# Clock_Sch.net
KiCad netlist of a schematic drawn in Altium Designer
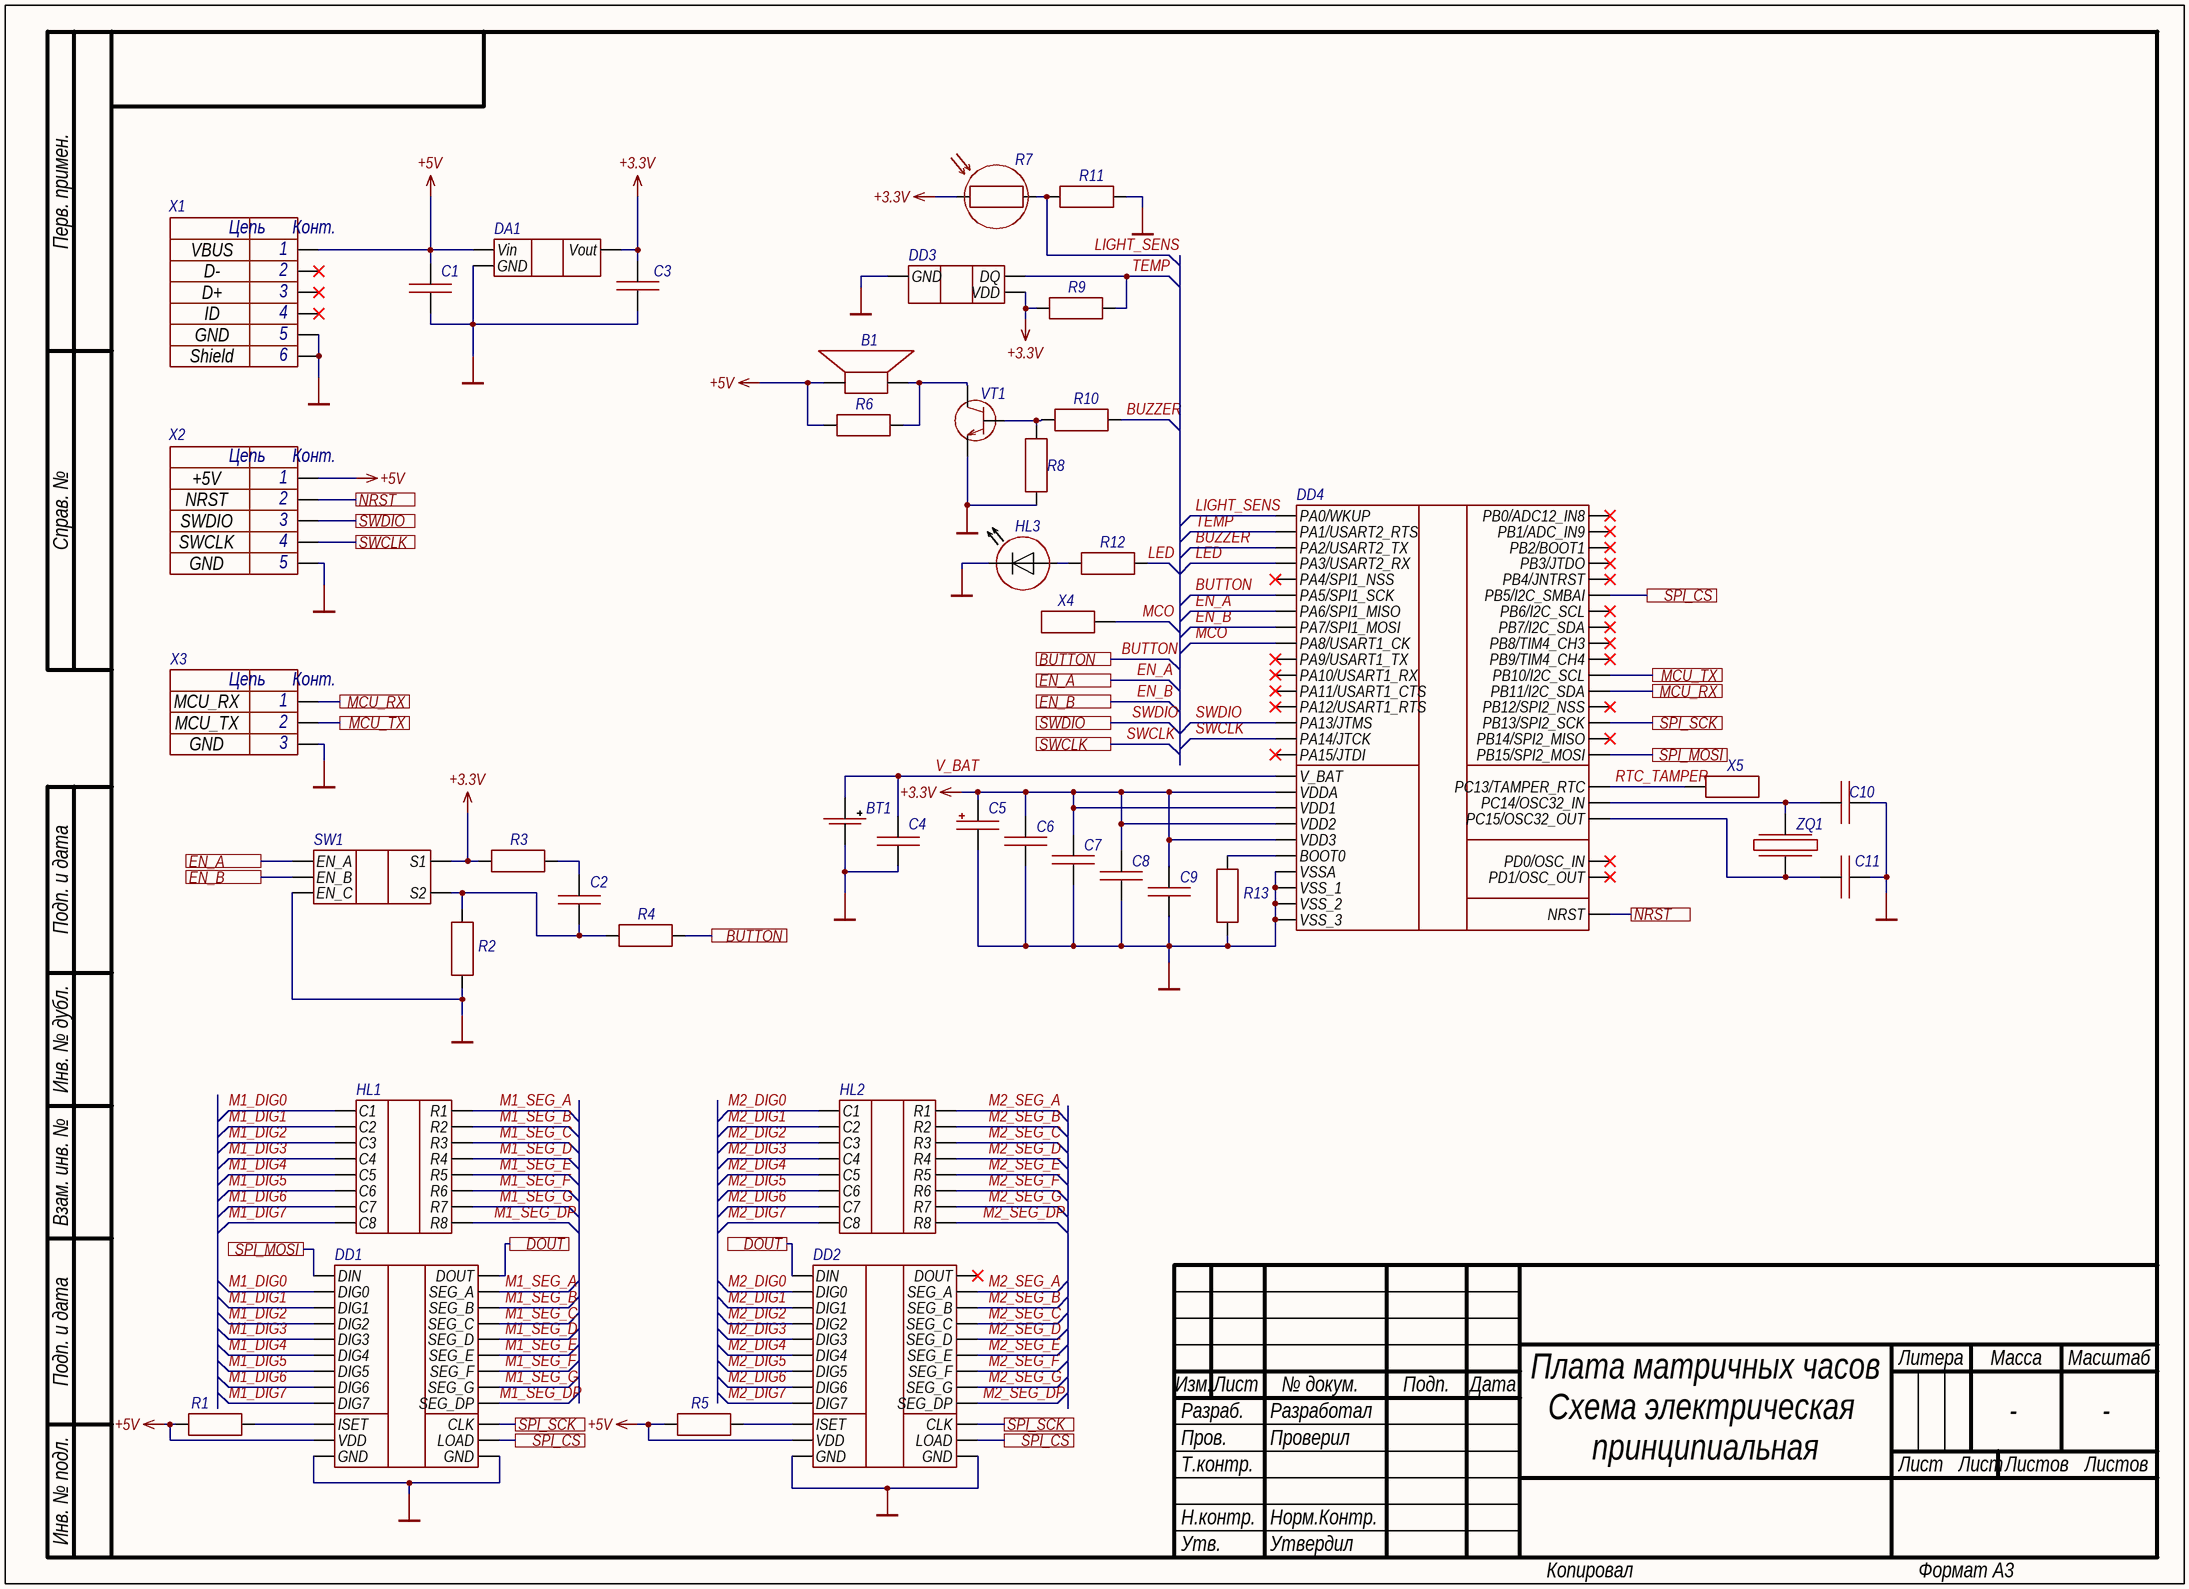
[diagram p0: Clock_Sch.SchDoc]

(export (version "E")
  (design (tool "Eeschema 10.0.6"))
  (components
    (comp (ref "B1")
      (value "AI-1223-TWT-12V-R")
      (footprint "Buzzer_12mm")
      (description "ELECTRO-MECHANICAL AUDIO INDICATOR")
      (libsource (lib "Indicators") (part "AI-1223-TWT-12V-R"))
    )
    (comp (ref "BT1")
      (value "CR-2032/F2N")
      (footprint "CR2032/F2N")
      (description "Coin, 20.0mm Lithium Manganese Dioxide 3 V Battery Non-Rechargeable (Primary)")
      (libsource (lib "Voltage Converters") (part "CR-2032/F2N"))
    )
    (comp (ref "C1")
      (value "C0603C334K4RACTU")
      (footprint "CAP_0603")
      (description "0.33 µF ±10% 16V Ceramic Capacitor X7R 0603 (1608 Metric)")
      (libsource (lib "Capacitors") (part "C0603C334K4RACTU"))
    )
    (comp (ref "C2")
      (value "C0603C104K9RACTU")
      (footprint "CAP_0603")
      (description "0.1 µF ±10% 6.3V Ceramic Capacitor X7R 0603 (1608 Metric)")
      (libsource (lib "Capacitors") (part "C0603C104K9RACTU"))
    )
    (comp (ref "C3")
      (value "C0603C104K9RACTU")
      (footprint "CAP_0603")
      (description "0.1 µF ±10% 6.3V Ceramic Capacitor X7R 0603 (1608 Metric)")
      (libsource (lib "Capacitors") (part "C0603C104K9RACTU"))
    )
    (comp (ref "C4")
      (value "C0603C104K9RACTU")
      (footprint "CAP_0603")
      (description "0.1 µF ±10% 6.3V Ceramic Capacitor X7R 0603 (1608 Metric)")
      (libsource (lib "Capacitors") (part "C0603C104K9RACTU"))
    )
    (comp (ref "C5")
      (value "T491A475K025AH")
      (footprint "CAP_A")
      (description "4.7uF 25V A CASE 10% (3.2 X 1.6 X 1.6mm) Inward L SMD 3216-18 6 Ohm 125°C Automotive T/R")
      (libsource (lib "Capacitors") (part "T491A475K025AH"))
    )
    (comp (ref "C6")
      (value "C0603C104K9RACTU")
      (footprint "CAP_0603")
      (description "0.1 µF ±10% 6.3V Ceramic Capacitor X7R 0603 (1608 Metric)")
      (libsource (lib "Capacitors") (part "C0603C104K9RACTU"))
    )
    (comp (ref "C7")
      (value "C0603C104K9RACTU")
      (footprint "CAP_0603")
      (description "0.1 µF ±10% 6.3V Ceramic Capacitor X7R 0603 (1608 Metric)")
      (libsource (lib "Capacitors") (part "C0603C104K9RACTU"))
    )
    (comp (ref "C8")
      (value "C0603C104K9RACTU")
      (footprint "CAP_0603")
      (description "0.1 µF ±10% 6.3V Ceramic Capacitor X7R 0603 (1608 Metric)")
      (libsource (lib "Capacitors") (part "C0603C104K9RACTU"))
    )
    (comp (ref "C9")
      (value "C0603C104K9RACTU")
      (footprint "CAP_0603")
      (description "0.1 µF ±10% 6.3V Ceramic Capacitor X7R 0603 (1608 Metric)")
      (libsource (lib "Capacitors") (part "C0603C104K9RACTU"))
    )
    (comp (ref "C10")
      (value "C0603C220G8GACTU")
      (footprint "CAP_0603")
      (description "22 pF ± 2% 10V Ceramic Capacitor 0603 (1608 metric)")
      (libsource (lib "Capacitors") (part "C0603C220G8GACTU"))
    )
    (comp (ref "C11")
      (value "C0603C220G8GACTU")
      (footprint "CAP_0603")
      (description "22 pF ± 2% 10V Ceramic Capacitor 0603 (1608 metric)")
      (libsource (lib "Capacitors") (part "C0603C220G8GACTU"))
    )
    (comp (ref "DA1")
      (value "L78L33ABUTR")
      (footprint "SOT-89")
      (description "Linear Voltage Regulators 3.3V 0.1A Positive")
      (libsource (lib "Voltage Converters") (part "L78L33ABUTR"))
    )
    (comp (ref "DD1")
      (value "MAX7219CWG")
      (footprint "SOIC-24W")
      (description "LED Display Drivers Serially Interfaced, 8-Digit, LED Display Drivers")
      (libsource (lib "Indicators") (part "MAX7219CWG"))
    )
    (comp (ref "DD2")
      (value "MAX7219CWG")
      (footprint "SOIC-24W")
      (description "LED Display Drivers Serially Interfaced, 8-Digit, LED Display Drivers")
      (libsource (lib "Indicators") (part "MAX7219CWG"))
    )
    (comp (ref "DD3")
      (value "DS18B20+")
      (footprint "TO-92")
      (description "Thermostats Programmable Resolution 1-Wire Digital Thermometer")
      (libsource (lib "Sensors") (part "DS18B20+"))
    )
    (comp (ref "DD4")
      (value "STM32F103C8T6")
      (footprint "LQFP48")
      (description "ARM Microcontrollers - MCU 32BIT Cortex M3 64KB 20KB RAM 2X12 ADC")
      (libsource (lib "Microcontrollers") (part "STM32F103C8T6"))
    )
    (comp (ref "HL1")
      (value "TC15-11GWA")
      (footprint "TC15-11")
      (description "LED Displays & Accessories Dot Matrix Grn 568nm Common Cathode")
      (libsource (lib "Indicators") (part "TC15-11GWA"))
    )
    (comp (ref "HL2")
      (value "TC15-11GWA")
      (footprint "TC15-11")
      (description "LED Displays & Accessories Dot Matrix Grn 568nm Common Cathode")
      (libsource (lib "Indicators") (part "TC15-11GWA"))
    )
    (comp (ref "HL3")
      (value "L_0805")
      (footprint "L_0805_Green")
      (description "0805 SMD LED")
      (libsource (lib "Indicators") (part "L_0805"))
    )
    (comp (ref "R1")
      (value "RC0805FR-0739KL")
      (footprint "Res_0805")
      (description "39 kOhm, 1% 0.125W 0805")
      (libsource (lib "Resistors") (part "RC0805FR-0739KL"))
    )
    (comp (ref "R2")
      (value "RC0805FR-071KL")
      (footprint "Res_0805")
      (description "1 kOhm, 1% 0.125W 0805")
      (libsource (lib "Resistors") (part "RC0805FR-071KL"))
    )
    (comp (ref "R3")
      (value "RC0805FR-07220RL")
      (footprint "Res_0805")
      (description "220 Ohm, 1% 0.125W 0805")
      (libsource (lib "Resistors") (part "RC0805FR-07220RL"))
    )
    (comp (ref "R4")
      (value "RC0805FR-07220RL")
      (footprint "Res_0805")
      (description "220 Ohm, 1% 0.125W 0805")
      (libsource (lib "Resistors") (part "RC0805FR-07220RL"))
    )
    (comp (ref "R5")
      (value "RC0805FR-0739KL")
      (footprint "Res_0805")
      (description "39 kOhm, 1% 0.125W 0805")
      (libsource (lib "Resistors") (part "RC0805FR-0739KL"))
    )
    (comp (ref "R6")
      (value "RC0805FR-071KL")
      (footprint "Res_0805")
      (description "1 kOhm, 1% 0.125W 0805")
      (libsource (lib "") (part "RC0805FR-071KL_1"))
    )
    (comp (ref "R7")
      (value "02-LDR2")
      (footprint "5mm LDR")
      (description "Photoresistor - 90mW - Light Resistance (10 Lux) 5 − 10Kohm - Dark Resistance 0.5Kohm - 5mm Dia")
      (libsource (lib "Sensors") (part "02-LDR2"))
    )
    (comp (ref "R8")
      (value "RC0805FR-0710KL")
      (footprint "Res_0805")
      (description "10 kOhm, 1% 0.125W 0805")
      (libsource (lib "") (part "RC0805FR-0710KL_1"))
    )
    (comp (ref "R9")
      (value "RC0805FR-074K7L")
      (footprint "Res_0805")
      (description "4.7 kOhm, 1% 0.125W 0805")
      (libsource (lib "Resistors") (part "RC0805FR-074K7L"))
    )
    (comp (ref "R10")
      (value "RC0805FR-071KL")
      (footprint "Res_0805")
      (description "1 kOhm, 1% 0.125W 0805")
      (libsource (lib "") (part "RC0805FR-071KL_1"))
    )
    (comp (ref "R11")
      (value "RC0805FR-0710KL")
      (footprint "Res_0805")
      (description "10 kOhm, 1% 0.125W 0805")
      (libsource (lib "Resistors") (part "RC0805FR-0710KL"))
    )
    (comp (ref "R12")
      (value "RC0805FR-071KL")
      (footprint "Res_0805")
      (description "1 kOhm, 1% 0.125W 0805")
      (libsource (lib "") (part "RC0805FR-071KL_1"))
    )
    (comp (ref "R13")
      (value "RC0805FR-071KL")
      (footprint "Res_0805")
      (description "1 kOhm, 1% 0.125W 0805")
      (libsource (lib "Resistors") (part "RC0805FR-071KL"))
    )
    (comp (ref "SW1")
      (value "EC12D1564402")
      (footprint "EC12D")
      (description "Encoder: incremental; Mounting: THT; 15imp/revol; 30000cycles")
      (libsource (lib "Switches") (part "EC12D1564402"))
    )
    (comp (ref "VT1")
      (value "BC817")
      (footprint "SOT-23")
      (description "Bipolar Transistors - BJT SOT23,NPN,0.8A,45V,GenPur")
      (libsource (lib "Transistors") (part "BC817"))
    )
    (comp (ref "X1")
      (value "47346-0001")
      (footprint "47346-0001")
      (description "USB - micro B USB 2.0 Receptacle Connector 5 Position Surface Mount, Right Angle")
      (libsource (lib "Connectors") (part "47346-0001"))
    )
    (comp (ref "X2")
      (value "PLS-5R (DS1022-1x5R)")
      (footprint "PLS-5 90' angle")
      (description "Male plug 2.54mm 1х5pin angled")
      (libsource (lib "Connectors") (part "PLS-5R (DS1022-1x5R)"))
    )
    (comp (ref "X3")
      (value "PLS-3 (DS1021-1x3)")
      (footprint "PLS-3")
      (description "Male plug 2.54mm 1x3pin straight type1")
      (libsource (lib "Connectors") (part "PLS-3 (DS1021-1x3)"))
    )
    (comp (ref "X4")
      (value "1-0.8-14-04")
      (footprint "1-0.8-14-04")
      (description "ГОСТ 16840-78")
      (libsource (lib "") (part "1-0.8-14-04_1"))
    )
    (comp (ref "X5")
      (value "1-0.8-14-04")
      (footprint "1-0.8-14-04")
      (description "ГОСТ 16840-78")
      (libsource (lib "Connectors") (part "1-0.8-14-04"))
    )
    (comp (ref "ZQ1")
      (value "MCRJ332768F1220HOW")
      (footprint "DT-38")
      (description "32.768kHz Crystal Resonator")
      (libsource (lib "XTALLs") (part "MCRJ332768F1220HOW"))
    )
  )
  (nets
    (net (code "1") (name "+3.3V") (class "Default")
      (node (ref "C3") (pin "2") (pinfunction "2_2") (pintype "passive"))
      (node (ref "C5") (pin "1") (pinfunction "1_1") (pintype "passive"))
      (node (ref "C6") (pin "2") (pinfunction "2_2") (pintype "passive"))
      (node (ref "C7") (pin "2") (pinfunction "2_2") (pintype "passive"))
      (node (ref "C8") (pin "2") (pinfunction "2_2") (pintype "passive"))
      (node (ref "C9") (pin "2") (pinfunction "2_2") (pintype "passive"))
      (node (ref "DA1") (pin "1") (pinfunction "Vout_1") (pintype "passive"))
      (node (ref "DD3") (pin "3") (pinfunction "VDD_3") (pintype "passive"))
      (node (ref "DD4") (pin "24") (pinfunction "VDD1_24") (pintype "passive"))
      (node (ref "DD4") (pin "36") (pinfunction "VDD2_36") (pintype "passive"))
      (node (ref "DD4") (pin "48") (pinfunction "VDD3_48") (pintype "passive"))
      (node (ref "DD4") (pin "9") (pinfunction "VDDA_9") (pintype "passive"))
      (node (ref "R3") (pin "1") (pinfunction "1_1") (pintype "passive"))
      (node (ref "R7") (pin "2") (pinfunction "2_2") (pintype "passive"))
      (node (ref "R9") (pin "2") (pinfunction "2_2") (pintype "passive"))
      (node (ref "SW1") (pin "D") (pinfunction "S1_D") (pintype "passive"))
    )
    (net (code "2") (name "+5V") (class "Default")
      (node (ref "B1") (pin "1") (pinfunction "1_1") (pintype "passive"))
      (node (ref "C1") (pin "2") (pinfunction "2_2") (pintype "passive"))
      (node (ref "DA1") (pin "3") (pinfunction "Vin_3") (pintype "passive"))
      (node (ref "DD1") (pin "19") (pinfunction "VDD_19") (pintype "passive"))
      (node (ref "DD2") (pin "19") (pinfunction "VDD_19") (pintype "passive"))
      (node (ref "R1") (pin "1") (pinfunction "1_1") (pintype "passive"))
      (node (ref "R5") (pin "1") (pinfunction "1_1") (pintype "passive"))
      (node (ref "R6") (pin "1") (pinfunction "1_1") (pintype "passive"))
      (node (ref "X1") (pin "1") (pinfunction "VBUS_1") (pintype "passive"))
      (node (ref "X2") (pin "1") (pinfunction "1_1") (pintype "passive"))
    )
    (net (code "3") (name "/BUTTON") (class "Default")
      (node (ref "DD4") (pin "15") (pinfunction "PA5/SPI1_SCK_15") (pintype "passive"))
      (node (ref "R4") (pin "2") (pinfunction "2_2") (pintype "passive"))
    )
    (net (code "4") (name "/BUZZER") (class "Default")
      (node (ref "DD4") (pin "12") (pinfunction "PA2/USART2_TX_12") (pintype "passive"))
      (node (ref "R10") (pin "2") (pinfunction "2_2") (pintype "passive"))
    )
    (net (code "5") (name "/DOUT") (class "Default")
      (node (ref "DD1") (pin "24") (pinfunction "DOUT_24") (pintype "passive"))
      (node (ref "DD2") (pin "1") (pinfunction "DIN_1") (pintype "passive"))
    )
    (net (code "6") (name "/EN_A") (class "Default")
      (node (ref "DD4") (pin "16") (pinfunction "PA6/SPI1_MISO_16") (pintype "passive"))
      (node (ref "SW1") (pin "A") (pinfunction "EN_A_A") (pintype "passive"))
    )
    (net (code "7") (name "/EN_B") (class "Default")
      (node (ref "DD4") (pin "17") (pinfunction "PA7/SPI1_MOSI_17") (pintype "passive"))
      (node (ref "SW1") (pin "B") (pinfunction "EN_B_B") (pintype "passive"))
    )
    (net (code "8") (name "/LED") (class "Default")
      (node (ref "DD4") (pin "13") (pinfunction "PA3/USART2_RX_13") (pintype "passive"))
      (node (ref "R12") (pin "2") (pinfunction "2_2") (pintype "passive"))
    )
    (net (code "9") (name "/LIGHT_SENS") (class "Default")
      (node (ref "DD4") (pin "10") (pinfunction "PA0/WKUP_10") (pintype "passive"))
      (node (ref "R11") (pin "2") (pinfunction "2_2") (pintype "passive"))
      (node (ref "R7") (pin "1") (pinfunction "1_1") (pintype "passive"))
    )
    (net (code "10") (name "/M1_DIG0") (class "Default")
      (node (ref "DD1") (pin "2") (pinfunction "DIG0_2") (pintype "passive"))
      (node (ref "HL1") (pin "13") (pinfunction "С1_13") (pintype "passive"))
    )
    (net (code "11") (name "/M1_DIG1") (class "Default")
      (node (ref "DD1") (pin "11") (pinfunction "DIG1_11") (pintype "passive"))
      (node (ref "HL1") (pin "3") (pinfunction "С2_3") (pintype "passive"))
    )
    (net (code "12") (name "/M1_DIG2") (class "Default")
      (node (ref "DD1") (pin "6") (pinfunction "DIG2_6") (pintype "passive"))
      (node (ref "HL1") (pin "4") (pinfunction "С3_4") (pintype "passive"))
    )
    (net (code "13") (name "/M1_DIG3") (class "Default")
      (node (ref "DD1") (pin "7") (pinfunction "DIG3_7") (pintype "passive"))
      (node (ref "HL1") (pin "10") (pinfunction "С4_10") (pintype "passive"))
    )
    (net (code "14") (name "/M1_DIG4") (class "Default")
      (node (ref "DD1") (pin "3") (pinfunction "DIG4_3") (pintype "passive"))
      (node (ref "HL1") (pin "6") (pinfunction "С5_6") (pintype "passive"))
    )
    (net (code "15") (name "/M1_DIG5") (class "Default")
      (node (ref "DD1") (pin "10") (pinfunction "DIG5_10") (pintype "passive"))
      (node (ref "HL1") (pin "11") (pinfunction "С6_11") (pintype "passive"))
    )
    (net (code "16") (name "/M1_DIG6") (class "Default")
      (node (ref "DD1") (pin "5") (pinfunction "DIG6_5") (pintype "passive"))
      (node (ref "HL1") (pin "15") (pinfunction "С7_15") (pintype "passive"))
    )
    (net (code "17") (name "/M1_DIG7") (class "Default")
      (node (ref "DD1") (pin "8") (pinfunction "DIG7_8") (pintype "passive"))
      (node (ref "HL1") (pin "16") (pinfunction "С8_16") (pintype "passive"))
    )
    (net (code "18") (name "/M1_SEG_A") (class "Default")
      (node (ref "DD1") (pin "14") (pinfunction "SEG_A_14") (pintype "passive"))
      (node (ref "HL1") (pin "9") (pinfunction "R1_9") (pintype "passive"))
    )
    (net (code "19") (name "/M1_SEG_B") (class "Default")
      (node (ref "DD1") (pin "16") (pinfunction "SEG_B_16") (pintype "passive"))
      (node (ref "HL1") (pin "14") (pinfunction "R2_14") (pintype "passive"))
    )
    (net (code "20") (name "/M1_SEG_C") (class "Default")
      (node (ref "DD1") (pin "20") (pinfunction "SEG_C_20") (pintype "passive"))
      (node (ref "HL1") (pin "8") (pinfunction "R3_8") (pintype "passive"))
    )
    (net (code "21") (name "/M1_SEG_D") (class "Default")
      (node (ref "DD1") (pin "23") (pinfunction "SEG_D_23") (pintype "passive"))
      (node (ref "HL1") (pin "12") (pinfunction "R4_12") (pintype "passive"))
    )
    (net (code "22") (name "/M1_SEG_DP") (class "Default")
      (node (ref "DD1") (pin "22") (pinfunction "SEG_DP_22") (pintype "passive"))
      (node (ref "HL1") (pin "5") (pinfunction "R8_5") (pintype "passive"))
    )
    (net (code "23") (name "/M1_SEG_E") (class "Default")
      (node (ref "DD1") (pin "21") (pinfunction "SEG_E_21") (pintype "passive"))
      (node (ref "HL1") (pin "1") (pinfunction "R5_1") (pintype "passive"))
    )
    (net (code "24") (name "/M1_SEG_F") (class "Default")
      (node (ref "DD1") (pin "15") (pinfunction "SEG_F_15") (pintype "passive"))
      (node (ref "HL1") (pin "7") (pinfunction "R6_7") (pintype "passive"))
    )
    (net (code "25") (name "/M1_SEG_G") (class "Default")
      (node (ref "DD1") (pin "17") (pinfunction "SEG_G_17") (pintype "passive"))
      (node (ref "HL1") (pin "2") (pinfunction "R7_2") (pintype "passive"))
    )
    (net (code "26") (name "/M2_DIG0") (class "Default")
      (node (ref "DD2") (pin "2") (pinfunction "DIG0_2") (pintype "passive"))
      (node (ref "HL2") (pin "13") (pinfunction "С1_13") (pintype "passive"))
    )
    (net (code "27") (name "/M2_DIG1") (class "Default")
      (node (ref "DD2") (pin "11") (pinfunction "DIG1_11") (pintype "passive"))
      (node (ref "HL2") (pin "3") (pinfunction "С2_3") (pintype "passive"))
    )
    (net (code "28") (name "/M2_DIG2") (class "Default")
      (node (ref "DD2") (pin "6") (pinfunction "DIG2_6") (pintype "passive"))
      (node (ref "HL2") (pin "4") (pinfunction "С3_4") (pintype "passive"))
    )
    (net (code "29") (name "/M2_DIG3") (class "Default")
      (node (ref "DD2") (pin "7") (pinfunction "DIG3_7") (pintype "passive"))
      (node (ref "HL2") (pin "10") (pinfunction "С4_10") (pintype "passive"))
    )
    (net (code "30") (name "/M2_DIG4") (class "Default")
      (node (ref "DD2") (pin "3") (pinfunction "DIG4_3") (pintype "passive"))
      (node (ref "HL2") (pin "6") (pinfunction "С5_6") (pintype "passive"))
    )
    (net (code "31") (name "/M2_DIG5") (class "Default")
      (node (ref "DD2") (pin "10") (pinfunction "DIG5_10") (pintype "passive"))
      (node (ref "HL2") (pin "11") (pinfunction "С6_11") (pintype "passive"))
    )
    (net (code "32") (name "/M2_DIG6") (class "Default")
      (node (ref "DD2") (pin "5") (pinfunction "DIG6_5") (pintype "passive"))
      (node (ref "HL2") (pin "15") (pinfunction "С7_15") (pintype "passive"))
    )
    (net (code "33") (name "/M2_DIG7") (class "Default")
      (node (ref "DD2") (pin "8") (pinfunction "DIG7_8") (pintype "passive"))
      (node (ref "HL2") (pin "16") (pinfunction "С8_16") (pintype "passive"))
    )
    (net (code "34") (name "/M2_SEG_A") (class "Default")
      (node (ref "DD2") (pin "14") (pinfunction "SEG_A_14") (pintype "passive"))
      (node (ref "HL2") (pin "9") (pinfunction "R1_9") (pintype "passive"))
    )
    (net (code "35") (name "/M2_SEG_B") (class "Default")
      (node (ref "DD2") (pin "16") (pinfunction "SEG_B_16") (pintype "passive"))
      (node (ref "HL2") (pin "14") (pinfunction "R2_14") (pintype "passive"))
    )
    (net (code "36") (name "/M2_SEG_C") (class "Default")
      (node (ref "DD2") (pin "20") (pinfunction "SEG_C_20") (pintype "passive"))
      (node (ref "HL2") (pin "8") (pinfunction "R3_8") (pintype "passive"))
    )
    (net (code "37") (name "/M2_SEG_D") (class "Default")
      (node (ref "DD2") (pin "23") (pinfunction "SEG_D_23") (pintype "passive"))
      (node (ref "HL2") (pin "12") (pinfunction "R4_12") (pintype "passive"))
    )
    (net (code "38") (name "/M2_SEG_DP") (class "Default")
      (node (ref "DD2") (pin "22") (pinfunction "SEG_DP_22") (pintype "passive"))
      (node (ref "HL2") (pin "5") (pinfunction "R8_5") (pintype "passive"))
    )
    (net (code "39") (name "/M2_SEG_E") (class "Default")
      (node (ref "DD2") (pin "21") (pinfunction "SEG_E_21") (pintype "passive"))
      (node (ref "HL2") (pin "1") (pinfunction "R5_1") (pintype "passive"))
    )
    (net (code "40") (name "/M2_SEG_F") (class "Default")
      (node (ref "DD2") (pin "15") (pinfunction "SEG_F_15") (pintype "passive"))
      (node (ref "HL2") (pin "7") (pinfunction "R6_7") (pintype "passive"))
    )
    (net (code "41") (name "/M2_SEG_G") (class "Default")
      (node (ref "DD2") (pin "17") (pinfunction "SEG_G_17") (pintype "passive"))
      (node (ref "HL2") (pin "2") (pinfunction "R7_2") (pintype "passive"))
    )
    (net (code "42") (name "/MCO") (class "Default")
      (node (ref "DD4") (pin "29") (pinfunction "PA8/USART1_CK_29") (pintype "passive"))
      (node (ref "X4") (pin "1") (pinfunction "1_1") (pintype "passive"))
    )
    (net (code "43") (name "/MCU_RX") (class "Default")
      (node (ref "DD4") (pin "22") (pinfunction "PB11/I2C_SDA_22") (pintype "passive"))
      (node (ref "X3") (pin "1") (pinfunction "1_1") (pintype "passive"))
    )
    (net (code "44") (name "/MCU_TX") (class "Default")
      (node (ref "DD4") (pin "21") (pinfunction "PB10/I2C_SCL_21") (pintype "passive"))
      (node (ref "X3") (pin "2") (pinfunction "2_2") (pintype "passive"))
    )
    (net (code "45") (name "/NRST") (class "Default")
      (node (ref "DD4") (pin "7") (pinfunction "NRST_7") (pintype "passive"))
      (node (ref "X2") (pin "2") (pinfunction "2_2") (pintype "passive"))
    )
    (net (code "46") (name "/RTC_TAMPER") (class "Default")
      (node (ref "DD4") (pin "2") (pinfunction "PC13/TAMPER_RTC_2") (pintype "passive"))
      (node (ref "X5") (pin "1") (pinfunction "1_1") (pintype "passive"))
    )
    (net (code "47") (name "/SPI_CS") (class "Default")
      (node (ref "DD1") (pin "12") (pinfunction "LOAD_12") (pintype "passive"))
      (node (ref "DD2") (pin "12") (pinfunction "LOAD_12") (pintype "passive"))
      (node (ref "DD4") (pin "41") (pinfunction "PB5/I2C_SMBAI_41") (pintype "passive"))
    )
    (net (code "48") (name "/SPI_MOSI") (class "Default")
      (node (ref "DD1") (pin "1") (pinfunction "DIN_1") (pintype "passive"))
      (node (ref "DD4") (pin "28") (pinfunction "PB15/SPI2_MOSI_28") (pintype "passive"))
    )
    (net (code "49") (name "/SPI_SCK") (class "Default")
      (node (ref "DD1") (pin "13") (pinfunction "CLK_13") (pintype "passive"))
      (node (ref "DD2") (pin "13") (pinfunction "CLK_13") (pintype "passive"))
      (node (ref "DD4") (pin "26") (pinfunction "PB13/SPI2_SCK_26") (pintype "passive"))
    )
    (net (code "50") (name "/SWCLK") (class "Default")
      (node (ref "DD4") (pin "37") (pinfunction "PA14/JTCK_37") (pintype "passive"))
      (node (ref "X2") (pin "4") (pinfunction "4_4") (pintype "passive"))
    )
    (net (code "51") (name "/SWDIO") (class "Default")
      (node (ref "DD4") (pin "34") (pinfunction "PA13/JTMS_34") (pintype "passive"))
      (node (ref "X2") (pin "3") (pinfunction "3_3") (pintype "passive"))
    )
    (net (code "52") (name "/TEMP") (class "Default")
      (node (ref "DD3") (pin "2") (pinfunction "DQ_2") (pintype "passive"))
      (node (ref "DD4") (pin "11") (pinfunction "PA1/USART2_RTS_11") (pintype "passive"))
      (node (ref "R9") (pin "1") (pinfunction "1_1") (pintype "passive"))
    )
    (net (code "53") (name "/V_BAT") (class "Default")
      (node (ref "BT1") (pin "1") (pinfunction "+_1") (pintype "passive"))
      (node (ref "C4") (pin "2") (pinfunction "2_2") (pintype "passive"))
      (node (ref "DD4") (pin "1") (pinfunction "V_BAT_1") (pintype "passive"))
    )
    (net (code "54") (name "GND") (class "Default")
      (node (ref "BT1") (pin "2") (pinfunction "-_2") (pintype "passive"))
      (node (ref "C1") (pin "1") (pinfunction "1_1") (pintype "passive"))
      (node (ref "C10") (pin "1") (pinfunction "1_1") (pintype "passive"))
      (node (ref "C11") (pin "1") (pinfunction "1_1") (pintype "passive"))
      (node (ref "C3") (pin "1") (pinfunction "1_1") (pintype "passive"))
      (node (ref "C4") (pin "1") (pinfunction "1_1") (pintype "passive"))
      (node (ref "C5") (pin "2") (pinfunction "2_2") (pintype "passive"))
      (node (ref "C6") (pin "1") (pinfunction "1_1") (pintype "passive"))
      (node (ref "C7") (pin "1") (pinfunction "1_1") (pintype "passive"))
      (node (ref "C8") (pin "1") (pinfunction "1_1") (pintype "passive"))
      (node (ref "C9") (pin "1") (pinfunction "1_1") (pintype "passive"))
      (node (ref "DA1") (pin "2") (pinfunction "GND_2") (pintype "passive"))
      (node (ref "DD1") (pin "4") (pinfunction "GND_4") (pintype "passive"))
      (node (ref "DD1") (pin "9") (pinfunction "GND_9") (pintype "passive"))
      (node (ref "DD2") (pin "4") (pinfunction "GND_4") (pintype "passive"))
      (node (ref "DD2") (pin "9") (pinfunction "GND_9") (pintype "passive"))
      (node (ref "DD3") (pin "1") (pinfunction "GND_1") (pintype "passive"))
      (node (ref "DD4") (pin "23") (pinfunction "VSS_1_23") (pintype "passive"))
      (node (ref "DD4") (pin "35") (pinfunction "VSS_2_35") (pintype "passive"))
      (node (ref "DD4") (pin "47") (pinfunction "VSS_3_47") (pintype "passive"))
      (node (ref "DD4") (pin "8") (pinfunction "VSSA_8") (pintype "passive"))
      (node (ref "HL3") (pin "2") (pinfunction "-_2") (pintype "passive"))
      (node (ref "R11") (pin "1") (pinfunction "1_1") (pintype "passive"))
      (node (ref "R13") (pin "1") (pinfunction "1_1") (pintype "passive"))
      (node (ref "R2") (pin "1") (pinfunction "1_1") (pintype "passive"))
      (node (ref "R8") (pin "1") (pinfunction "1_1") (pintype "passive"))
      (node (ref "SW1") (pin "C") (pinfunction "EN_C_C") (pintype "passive"))
      (node (ref "VT1") (pin "2") (pinfunction "Emitter_2") (pintype "passive"))
      (node (ref "X1") (pin "5") (pinfunction "GND_5") (pintype "passive"))
      (node (ref "X1") (pin "6") (pinfunction "Shield_6") (pintype "passive"))
      (node (ref "X2") (pin "5") (pinfunction "5_5") (pintype "passive"))
      (node (ref "X3") (pin "3") (pinfunction "3_3") (pintype "passive"))
    )
    (net (code "55") (name "Net-(C2-Pad2)") (class "Default")
      (node (ref "C2") (pin "2") (pinfunction "2_2") (pintype "passive"))
      (node (ref "R3") (pin "2") (pinfunction "2_2") (pintype "passive"))
    )
    (net (code "56") (name "Net-(DD1-ISET)") (class "Default")
      (node (ref "DD1") (pin "18") (pinfunction "ISET_18") (pintype "passive"))
      (node (ref "R1") (pin "2") (pinfunction "2_2") (pintype "passive"))
    )
    (net (code "57") (name "Net-(DD2-ISET)") (class "Default")
      (node (ref "DD2") (pin "18") (pinfunction "ISET_18") (pintype "passive"))
      (node (ref "R5") (pin "2") (pinfunction "2_2") (pintype "passive"))
    )
    (net (code "58") (name "Net-(DD4-BOOT0)") (class "Default")
      (node (ref "DD4") (pin "44") (pinfunction "BOOT0_44") (pintype "passive"))
      (node (ref "R13") (pin "2") (pinfunction "2_2") (pintype "passive"))
    )
    (net (code "59") (name "Net-(DD4-PC14{slash}OSC32_IN)") (class "Default")
      (node (ref "C10") (pin "2") (pinfunction "2_2") (pintype "passive"))
      (node (ref "DD4") (pin "3") (pinfunction "PC14/OSC32_IN_3") (pintype "passive"))
      (node (ref "ZQ1") (pin "2") (pinfunction "2_2") (pintype "passive"))
    )
    (net (code "60") (name "Net-(DD4-PC15{slash}OSC32_OUT)") (class "Default")
      (node (ref "C11") (pin "2") (pinfunction "2_2") (pintype "passive"))
      (node (ref "DD4") (pin "4") (pinfunction "PC15/OSC32_OUT_4") (pintype "passive"))
      (node (ref "ZQ1") (pin "1") (pinfunction "1_1") (pintype "passive"))
    )
    (net (code "61") (name "Net-(HL3-+)") (class "Default")
      (node (ref "HL3") (pin "1") (pinfunction "+_1") (pintype "passive"))
      (node (ref "R12") (pin "1") (pinfunction "1_1") (pintype "passive"))
    )
    (net (code "62") (name "Net-(SW1-S2)") (class "Default")
      (node (ref "C2") (pin "1") (pinfunction "1_1") (pintype "passive"))
      (node (ref "R2") (pin "2") (pinfunction "2_2") (pintype "passive"))
      (node (ref "R4") (pin "1") (pinfunction "1_1") (pintype "passive"))
      (node (ref "SW1") (pin "E") (pinfunction "S2_E") (pintype "passive"))
    )
    (net (code "63") (name "Net-(VT1-BASE)") (class "Default")
      (node (ref "R10") (pin "1") (pinfunction "1_1") (pintype "passive"))
      (node (ref "R8") (pin "2") (pinfunction "2_2") (pintype "passive"))
      (node (ref "VT1") (pin "1") (pinfunction "BASE_1") (pintype "passive"))
    )
    (net (code "64") (name "Net-(VT1-Collector)") (class "Default")
      (node (ref "B1") (pin "2") (pinfunction "2_2") (pintype "passive"))
      (node (ref "R6") (pin "2") (pinfunction "2_2") (pintype "passive"))
      (node (ref "VT1") (pin "3") (pinfunction "Collector_3") (pintype "passive"))
    )
    (net (code "65") (name "unconnected-(DD2-DOUT-Pad24)") (class "Default")
      (node (ref "DD2") (pin "24") (pinfunction "DOUT_24") (pintype "passive+no_connect"))
    )
    (net (code "66") (name "unconnected-(DD4-PA4{slash}SPI1_NSS-Pad14)") (class "Default")
      (node (ref "DD4") (pin "14") (pinfunction "PA4/SPI1_NSS_14") (pintype "passive+no_connect"))
    )
    (net (code "67") (name "unconnected-(DD4-PA9{slash}USART1_TX-Pad30)") (class "Default")
      (node (ref "DD4") (pin "30") (pinfunction "PA9/USART1_TX_30") (pintype "passive+no_connect"))
    )
    (net (code "68") (name "unconnected-(DD4-PA10{slash}USART1_RX-Pad31)") (class "Default")
      (node (ref "DD4") (pin "31") (pinfunction "PA10/USART1_RX_31") (pintype "passive+no_connect"))
    )
    (net (code "69") (name "unconnected-(DD4-PA11{slash}USART1_CTS-Pad32)") (class "Default")
      (node (ref "DD4") (pin "32") (pinfunction "PA11/USART1_CTS_32") (pintype "passive+no_connect"))
    )
    (net (code "70") (name "unconnected-(DD4-PA12{slash}USART1_RTS-Pad33)") (class "Default")
      (node (ref "DD4") (pin "33") (pinfunction "PA12/USART1_RTS_33") (pintype "passive+no_connect"))
    )
    (net (code "71") (name "unconnected-(DD4-PA15{slash}JTDI-Pad38)") (class "Default")
      (node (ref "DD4") (pin "38") (pinfunction "PA15/JTDI_38") (pintype "passive+no_connect"))
    )
    (net (code "72") (name "unconnected-(DD4-PB0{slash}ADC12_IN8-Pad18)") (class "Default")
      (node (ref "DD4") (pin "18") (pinfunction "PB0/ADC12_IN8_18") (pintype "passive+no_connect"))
    )
    (net (code "73") (name "unconnected-(DD4-PB1{slash}ADC_IN9-Pad19)") (class "Default")
      (node (ref "DD4") (pin "19") (pinfunction "PB1/ADC_IN9_19") (pintype "passive+no_connect"))
    )
    (net (code "74") (name "unconnected-(DD4-PB2{slash}BOOT1-Pad20)") (class "Default")
      (node (ref "DD4") (pin "20") (pinfunction "PB2/BOOT1_20") (pintype "passive+no_connect"))
    )
    (net (code "75") (name "unconnected-(DD4-PB3{slash}JTDO-Pad39)") (class "Default")
      (node (ref "DD4") (pin "39") (pinfunction "PB3/JTDO_39") (pintype "passive+no_connect"))
    )
    (net (code "76") (name "unconnected-(DD4-PB4{slash}JNTRST-Pad40)") (class "Default")
      (node (ref "DD4") (pin "40") (pinfunction "PB4/JNTRST_40") (pintype "passive+no_connect"))
    )
    (net (code "77") (name "unconnected-(DD4-PB6{slash}I2C_SCL-Pad42)") (class "Default")
      (node (ref "DD4") (pin "42") (pinfunction "PB6/I2C_SCL_42") (pintype "passive+no_connect"))
    )
    (net (code "78") (name "unconnected-(DD4-PB7{slash}I2C_SDA-Pad43)") (class "Default")
      (node (ref "DD4") (pin "43") (pinfunction "PB7/I2C_SDA_43") (pintype "passive+no_connect"))
    )
    (net (code "79") (name "unconnected-(DD4-PB8{slash}TIM4_CH3-Pad45)") (class "Default")
      (node (ref "DD4") (pin "45") (pinfunction "PB8/TIM4_CH3_45") (pintype "passive+no_connect"))
    )
    (net (code "80") (name "unconnected-(DD4-PB9{slash}TIM4_CH4-Pad46)") (class "Default")
      (node (ref "DD4") (pin "46") (pinfunction "PB9/TIM4_CH4_46") (pintype "passive+no_connect"))
    )
    (net (code "81") (name "unconnected-(DD4-PB12{slash}SPI2_NSS-Pad25)") (class "Default")
      (node (ref "DD4") (pin "25") (pinfunction "PB12/SPI2_NSS_25") (pintype "passive+no_connect"))
    )
    (net (code "82") (name "unconnected-(DD4-PB14{slash}SPI2_MISO-Pad27)") (class "Default")
      (node (ref "DD4") (pin "27") (pinfunction "PB14/SPI2_MISO_27") (pintype "passive+no_connect"))
    )
    (net (code "83") (name "unconnected-(DD4-PD0{slash}OSC_IN-Pad5)") (class "Default")
      (node (ref "DD4") (pin "5") (pinfunction "PD0/OSC_IN_5") (pintype "passive+no_connect"))
    )
    (net (code "84") (name "unconnected-(DD4-PD1{slash}OSC_OUT-Pad6)") (class "Default")
      (node (ref "DD4") (pin "6") (pinfunction "PD1/OSC_OUT_6") (pintype "passive+no_connect"))
    )
    (net (code "85") (name "unconnected-(X1-D+-Pad3)") (class "Default")
      (node (ref "X1") (pin "3") (pinfunction "D+_3") (pintype "passive+no_connect"))
    )
    (net (code "86") (name "unconnected-(X1-D--Pad2)") (class "Default")
      (node (ref "X1") (pin "2") (pinfunction "D-_2") (pintype "passive+no_connect"))
    )
    (net (code "87") (name "unconnected-(X1-ID-Pad4)") (class "Default")
      (node (ref "X1") (pin "4") (pinfunction "ID_4") (pintype "passive+no_connect"))
    )
  )
)
